# fire_warning_system.net
KiCad netlist of a schematic drawn in Altium Designer
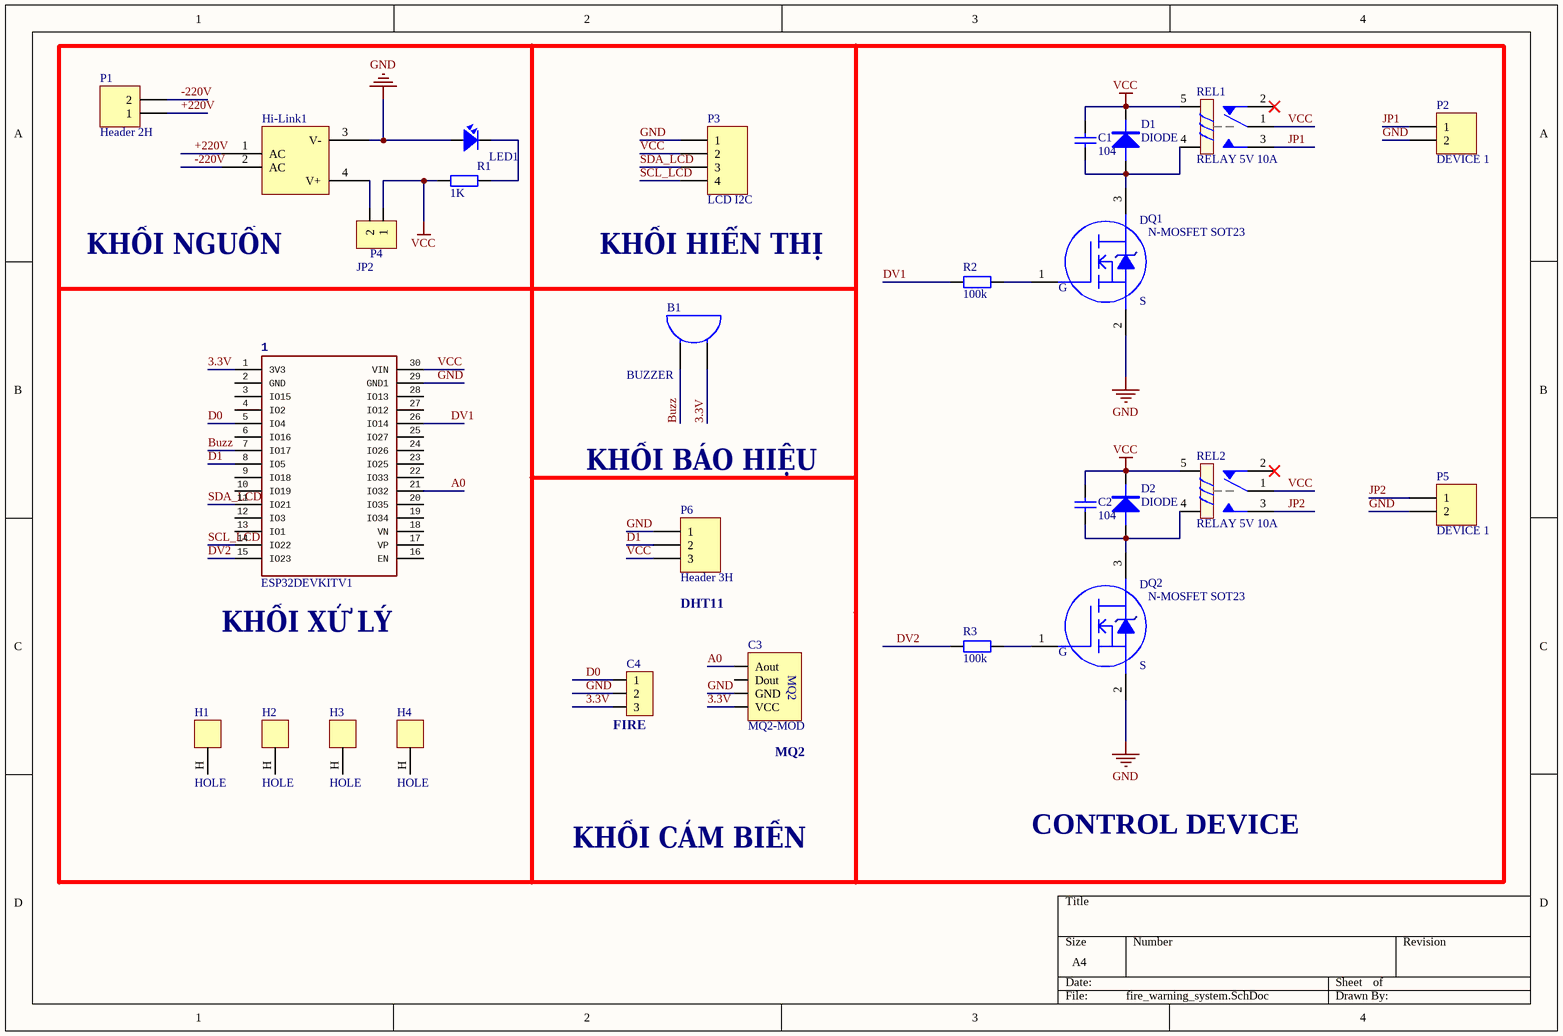
[diagram p0: fire_warning_system.SchDoc]

(export (version "E")
  (design (tool "Eeschema 10.0.6"))
  (components
    (comp (ref "1")
      (value "ESP32DEVKITV1")
      (footprint "ESP32-DEVKITV1")
      (libsource (lib "ESP32-DEVKITV1") (part "ESP32DEVKITV1"))
    )
    (comp (ref "B1")
      (value "BUZZER")
      (footprint "SPEAKER")
      (libsource (lib "ThinhNguyenLib") (part "BUZZER"))
    )
    (comp (ref "C1")
      (value "104")
      (footprint "0805 CAP")
      (fields (field (name "PUBLISHER") "Altium Limited"))
      (libsource (lib "THINHDUILIB") (part "CAP CERAMIC"))
    )
    (comp (ref "C2")
      (value "104")
      (footprint "0805 CAP")
      (fields (field (name "PUBLISHER") "Altium Limited"))
      (libsource (lib "THINHDUILIB") (part "CAP CERAMIC"))
    )
    (comp (ref "C3")
      (value "MQ2-MOD")
      (footprint "MQ2-MODULE")
      (fields
        (field (name "MANUFACTURER") "Würth Elektronik eiSos GmbH")
        (field (name "PARTNO") "613004143121")
        (field (name "CREATED BY") "Karrer Zheng")
      )
      (libsource (lib "LIBRARY") (part "MQ2-MOD"))
    )
    (comp (ref "C4")
      (value "Hồng ngoại")
      (footprint "JP3-C1T")
      (description "Header IDC, 3 x 1 Pin Vertical 2.54mm Pitch (Non-Boxed, Male)")
      (fields
        (field (name "MANUFACTURER") "Würth Elektronik eiSos GmbH")
        (field (name "PARTNO") "613002143121")
        (field (name "CREATED BY") "Karrer Zheng")
      )
      (libsource (lib "LIBRARY") (part "Header3"))
    )
    (comp (ref "D1") (value "DIODE") (footprint "DIODE SMA") (libsource (lib "THINHDUILIB") (part "DIODE")))
    (comp (ref "D2") (value "DIODE") (footprint "DIODE SMA") (libsource (lib "THINHDUILIB") (part "DIODE")))
    (comp (ref "H1") (value "HOLE") (footprint "HOLE") (libsource (lib "ThinhNguyenLib") (part "HOLE")))
    (comp (ref "H2") (value "HOLE") (footprint "HOLE") (libsource (lib "ThinhNguyenLib") (part "HOLE")))
    (comp (ref "H3") (value "HOLE") (footprint "HOLE") (libsource (lib "ThinhNguyenLib") (part "HOLE")))
    (comp (ref "H4") (value "HOLE") (footprint "HOLE") (libsource (lib "ThinhNguyenLib") (part "HOLE")))
    (comp (ref "Hi-Link1")
      (value "Component_1")
      (footprint "5/12V-3W")
      (libsource (lib "HI-LINK") (part "Component_1"))
    )
    (comp (ref "LED1")
      (value "LED")
      (footprint "LED SMD 0805")
      (description "LED Single colour Green and Red")
      (libsource (lib "LIBRARY") (part "LED"))
    )
    (comp (ref "P1")
      (value "Header 2H")
      (footprint "CON 2KF 5.08MM")
      (fields (field (name "PUBLISHER") "Altium Limited"))
      (libsource (lib "ThinhNguyenLib") (part "Header 2H"))
    )
    (comp (ref "P2")
      (value "DEVICE 1")
      (footprint "CON 2KF 5.08MM")
      (fields (field (name "PUBLISHER") "Altium Limited"))
      (libsource (lib "THINHDUILIB") (part "Header 2H"))
    )
    (comp (ref "P3")
      (value "LCD I2C")
      (footprint "HDR1X4")
      (fields (field (name "PUBLISHER") "Altium Limited"))
      (libsource (lib "ThinhNguyenLib") (part "Header 4H"))
    )
    (comp (ref "P4")
      (value "JP2")
      (footprint "JUMPER PITCH 2 PIN")
      (description "WR-PHD 2.54 mm Angled Socket Header")
      (fields
        (field (name "MANUFACTURER") "Würth Elektronik eiSos GmbH")
        (field (name "PARTNO") "613002143121")
        (field (name "CREATED BY") "Karrer Zheng")
      )
      (libsource (lib "LIBRARY") (part "JP2"))
    )
    (comp (ref "P5")
      (value "DEVICE 1")
      (footprint "CON 2KF 5.08MM")
      (fields (field (name "PUBLISHER") "Altium Limited"))
      (libsource (lib "THINHDUILIB") (part "Header 2H"))
    )
    (comp (ref "P6")
      (value "Header 3H")
      (footprint "HDR1X3")
      (fields (field (name "PUBLISHER") "Altium Limited"))
      (libsource (lib "ThinhNguyenLib") (part "Header 3H"))
    )
    (comp (ref "Q1")
      (value "N-MOSFET SOT23")
      (footprint "TO-92 - 2N7000")
      (libsource (lib "ThinhNguyenLib") (part "N-MOSFET SOT23"))
    )
    (comp (ref "Q2")
      (value "N-MOSFET SOT23")
      (footprint "TO-92 - 2N7000")
      (libsource (lib "ThinhNguyenLib") (part "N-MOSFET SOT23"))
    )
    (comp (ref "R1")
      (value "1K")
      (footprint "0805 RESISTOR")
      (libsource (lib "ThinhNguyenLib") (part "RESISTOR"))
    )
    (comp (ref "R2")
      (value "100k")
      (footprint "0805 RESISTOR")
      (libsource (lib "THINHDUILIB") (part "RESISTOR"))
    )
    (comp (ref "R3")
      (value "100k")
      (footprint "0805 RESISTOR")
      (libsource (lib "THINHDUILIB") (part "RESISTOR"))
    )
    (comp (ref "REL1")
      (value "RELAY 5V 10A")
      (footprint "RELAY 5V-10A")
      (libsource (lib "ThinhNguyenLib") (part "RELAY 5V 10A"))
    )
    (comp (ref "REL2")
      (value "RELAY 5V 10A")
      (footprint "RELAY 5V-10A")
      (libsource (lib "ThinhNguyenLib") (part "RELAY 5V 10A"))
    )
  )
  (nets
    (net (code "1") (name "/+220V") (class "Default")
      (node (ref "Hi-Link1") (pin "1") (pinfunction "AC_1") (pintype "passive"))
      (node (ref "P1") (pin "1") (pinfunction "1_1") (pintype "passive"))
    )
    (net (code "2") (name "/-220V") (class "Default")
      (node (ref "Hi-Link1") (pin "2") (pinfunction "AC_2") (pintype "passive"))
      (node (ref "P1") (pin "2") (pinfunction "2_2") (pintype "passive"))
    )
    (net (code "3") (name "/3.3V") (class "Default")
      (node (ref "1") (pin "1") (pinfunction "3V3_1") (pintype "passive"))
      (node (ref "B1") (pin "2") (pinfunction "B_2") (pintype "passive"))
      (node (ref "C3") (pin "4") (pinfunction "VCC_4") (pintype "passive"))
      (node (ref "C4") (pin "3") (pinfunction "3_3") (pintype "passive"))
    )
    (net (code "4") (name "/A0") (class "Default")
      (node (ref "1") (pin "21") (pinfunction "IO32_21") (pintype "passive"))
      (node (ref "C3") (pin "1") (pinfunction "Aout_1") (pintype "passive"))
    )
    (net (code "5") (name "/Buzz") (class "Default")
      (node (ref "1") (pin "7") (pinfunction "IO17_7") (pintype "passive"))
      (node (ref "B1") (pin "1") (pinfunction "A_1") (pintype "passive"))
    )
    (net (code "6") (name "/D0") (class "Default")
      (node (ref "1") (pin "5") (pinfunction "IO4_5") (pintype "passive"))
      (node (ref "C4") (pin "1") (pinfunction "1_1") (pintype "passive"))
    )
    (net (code "7") (name "/D1") (class "Default")
      (node (ref "1") (pin "8") (pinfunction "IO5_8") (pintype "passive"))
      (node (ref "P6") (pin "2") (pinfunction "2_2") (pintype "passive"))
    )
    (net (code "8") (name "/DV1") (class "Default")
      (node (ref "1") (pin "26") (pinfunction "IO14_26") (pintype "passive"))
      (node (ref "R2") (pin "2") (pinfunction "2_2") (pintype "passive"))
    )
    (net (code "9") (name "/DV2") (class "Default")
      (node (ref "1") (pin "15") (pinfunction "IO23_15") (pintype "passive"))
      (node (ref "R3") (pin "2") (pinfunction "2_2") (pintype "passive"))
    )
    (net (code "10") (name "/JP1") (class "Default")
      (node (ref "P2") (pin "1") (pinfunction "1_1") (pintype "passive"))
      (node (ref "REL1") (pin "3") (pinfunction "3_3") (pintype "passive"))
    )
    (net (code "11") (name "/JP2") (class "Default")
      (node (ref "P5") (pin "1") (pinfunction "1_1") (pintype "passive"))
      (node (ref "REL2") (pin "3") (pinfunction "3_3") (pintype "passive"))
    )
    (net (code "12") (name "/SCL_LCD") (class "Default")
      (node (ref "1") (pin "14") (pinfunction "IO22_14") (pintype "passive"))
      (node (ref "P3") (pin "4") (pinfunction "4_4") (pintype "passive"))
    )
    (net (code "13") (name "/SDA_LCD") (class "Default")
      (node (ref "1") (pin "11") (pinfunction "IO21_11") (pintype "passive"))
      (node (ref "P3") (pin "3") (pinfunction "3_3") (pintype "passive"))
    )
    (net (code "14") (name "GND") (class "Default")
      (node (ref "1") (pin "29") (pinfunction "GND1_29") (pintype "passive"))
      (node (ref "C3") (pin "3") (pinfunction "GND_3") (pintype "passive"))
      (node (ref "C4") (pin "2") (pinfunction "2_2") (pintype "passive"))
      (node (ref "Hi-Link1") (pin "3") (pinfunction "V-_3") (pintype "passive"))
      (node (ref "LED1") (pin "1") (pinfunction "1_1") (pintype "passive"))
      (node (ref "P2") (pin "2") (pinfunction "2_2") (pintype "passive"))
      (node (ref "P3") (pin "1") (pinfunction "1_1") (pintype "passive"))
      (node (ref "P5") (pin "2") (pinfunction "2_2") (pintype "passive"))
      (node (ref "P6") (pin "1") (pinfunction "1_1") (pintype "passive"))
      (node (ref "Q1") (pin "2") (pinfunction "S_2") (pintype "passive"))
      (node (ref "Q2") (pin "2") (pinfunction "S_2") (pintype "passive"))
    )
    (net (code "15") (name "Net-(Hi-Link1-V+)") (class "Default")
      (node (ref "Hi-Link1") (pin "4") (pinfunction "V+_4") (pintype "passive"))
      (node (ref "P4") (pin "2") (pinfunction "2_2") (pintype "passive"))
    )
    (net (code "16") (name "Net-(LED1-Pad2)") (class "Default")
      (node (ref "LED1") (pin "2") (pinfunction "2_2") (pintype "passive"))
      (node (ref "R1") (pin "2") (pinfunction "2_2") (pintype "passive"))
    )
    (net (code "17") (name "Net-(Q1-D)") (class "Default")
      (node (ref "C1") (pin "2") (pinfunction "2_2") (pintype "passive"))
      (node (ref "D1") (pin "1") (pinfunction "1_1") (pintype "passive"))
      (node (ref "Q1") (pin "3") (pinfunction "D_3") (pintype "passive"))
      (node (ref "REL1") (pin "4") (pinfunction "4_4") (pintype "passive"))
    )
    (net (code "18") (name "Net-(Q1-G)") (class "Default")
      (node (ref "Q1") (pin "1") (pinfunction "G_1") (pintype "passive"))
      (node (ref "R2") (pin "1") (pinfunction "1_1") (pintype "passive"))
    )
    (net (code "19") (name "Net-(Q2-D)") (class "Default")
      (node (ref "C2") (pin "2") (pinfunction "2_2") (pintype "passive"))
      (node (ref "D2") (pin "1") (pinfunction "1_1") (pintype "passive"))
      (node (ref "Q2") (pin "3") (pinfunction "D_3") (pintype "passive"))
      (node (ref "REL2") (pin "4") (pinfunction "4_4") (pintype "passive"))
    )
    (net (code "20") (name "Net-(Q2-G)") (class "Default")
      (node (ref "Q2") (pin "1") (pinfunction "G_1") (pintype "passive"))
      (node (ref "R3") (pin "1") (pinfunction "1_1") (pintype "passive"))
    )
    (net (code "21") (name "VCC") (class "Default")
      (node (ref "1") (pin "30") (pinfunction "VIN_30") (pintype "passive"))
      (node (ref "C1") (pin "1") (pinfunction "1_1") (pintype "passive"))
      (node (ref "C2") (pin "1") (pinfunction "1_1") (pintype "passive"))
      (node (ref "D1") (pin "2") (pinfunction "2_2") (pintype "passive"))
      (node (ref "D2") (pin "2") (pinfunction "2_2") (pintype "passive"))
      (node (ref "P3") (pin "2") (pinfunction "2_2") (pintype "passive"))
      (node (ref "P4") (pin "1") (pinfunction "1_1") (pintype "passive"))
      (node (ref "P6") (pin "3") (pinfunction "3_3") (pintype "passive"))
      (node (ref "R1") (pin "1") (pinfunction "1_1") (pintype "passive"))
      (node (ref "REL1") (pin "1") (pinfunction "1_1") (pintype "passive"))
      (node (ref "REL1") (pin "5") (pinfunction "5_5") (pintype "passive"))
      (node (ref "REL2") (pin "1") (pinfunction "1_1") (pintype "passive"))
      (node (ref "REL2") (pin "5") (pinfunction "5_5") (pintype "passive"))
    )
    (net (code "22") (name "unconnected-(1-EN-Pad16)") (class "Default")
      (node (ref "1") (pin "16") (pinfunction "EN_16") (pintype "passive"))
    )
    (net (code "23") (name "unconnected-(1-GND-Pad2)") (class "Default")
      (node (ref "1") (pin "2") (pinfunction "GND_2") (pintype "passive"))
    )
    (net (code "24") (name "unconnected-(1-IO1-Pad13)") (class "Default")
      (node (ref "1") (pin "13") (pinfunction "IO1_13") (pintype "passive"))
    )
    (net (code "25") (name "unconnected-(1-IO2-Pad4)") (class "Default")
      (node (ref "1") (pin "4") (pinfunction "IO2_4") (pintype "passive"))
    )
    (net (code "26") (name "unconnected-(1-IO3-Pad12)") (class "Default")
      (node (ref "1") (pin "12") (pinfunction "IO3_12") (pintype "passive"))
    )
    (net (code "27") (name "unconnected-(1-IO12-Pad27)") (class "Default")
      (node (ref "1") (pin "27") (pinfunction "IO12_27") (pintype "passive"))
    )
    (net (code "28") (name "unconnected-(1-IO13-Pad28)") (class "Default")
      (node (ref "1") (pin "28") (pinfunction "IO13_28") (pintype "passive"))
    )
    (net (code "29") (name "unconnected-(1-IO15-Pad3)") (class "Default")
      (node (ref "1") (pin "3") (pinfunction "IO15_3") (pintype "passive"))
    )
    (net (code "30") (name "unconnected-(1-IO16-Pad6)") (class "Default")
      (node (ref "1") (pin "6") (pinfunction "IO16_6") (pintype "passive"))
    )
    (net (code "31") (name "unconnected-(1-IO18-Pad9)") (class "Default")
      (node (ref "1") (pin "9") (pinfunction "IO18_9") (pintype "passive"))
    )
    (net (code "32") (name "unconnected-(1-IO19-Pad10)") (class "Default")
      (node (ref "1") (pin "10") (pinfunction "IO19_10") (pintype "passive"))
    )
    (net (code "33") (name "unconnected-(1-IO25-Pad23)") (class "Default")
      (node (ref "1") (pin "23") (pinfunction "IO25_23") (pintype "passive"))
    )
    (net (code "34") (name "unconnected-(1-IO26-Pad24)") (class "Default")
      (node (ref "1") (pin "24") (pinfunction "IO26_24") (pintype "passive"))
    )
    (net (code "35") (name "unconnected-(1-IO27-Pad25)") (class "Default")
      (node (ref "1") (pin "25") (pinfunction "IO27_25") (pintype "passive"))
    )
    (net (code "36") (name "unconnected-(1-IO33-Pad22)") (class "Default")
      (node (ref "1") (pin "22") (pinfunction "IO33_22") (pintype "passive"))
    )
    (net (code "37") (name "unconnected-(1-IO34-Pad19)") (class "Default")
      (node (ref "1") (pin "19") (pinfunction "IO34_19") (pintype "passive"))
    )
    (net (code "38") (name "unconnected-(1-IO35-Pad20)") (class "Default")
      (node (ref "1") (pin "20") (pinfunction "IO35_20") (pintype "passive"))
    )
    (net (code "39") (name "unconnected-(1-VN-Pad18)") (class "Default")
      (node (ref "1") (pin "18") (pinfunction "VN_18") (pintype "passive"))
    )
    (net (code "40") (name "unconnected-(1-VP-Pad17)") (class "Default")
      (node (ref "1") (pin "17") (pinfunction "VP_17") (pintype "passive"))
    )
    (net (code "41") (name "unconnected-(C3-Dout-Pad2)") (class "Default")
      (node (ref "C3") (pin "2") (pinfunction "Dout_2") (pintype "passive"))
    )
    (net (code "42") (name "unconnected-(H1-HOLE-PadH)") (class "Default")
      (node (ref "H1") (pin "H") (pinfunction "HOLE_H") (pintype "passive"))
    )
    (net (code "43") (name "unconnected-(H2-HOLE-PadH)") (class "Default")
      (node (ref "H2") (pin "H") (pinfunction "HOLE_H") (pintype "passive"))
    )
    (net (code "44") (name "unconnected-(H3-HOLE-PadH)") (class "Default")
      (node (ref "H3") (pin "H") (pinfunction "HOLE_H") (pintype "passive"))
    )
    (net (code "45") (name "unconnected-(H4-HOLE-PadH)") (class "Default")
      (node (ref "H4") (pin "H") (pinfunction "HOLE_H") (pintype "passive"))
    )
    (net (code "46") (name "unconnected-(REL1-Pad2)") (class "Default")
      (node (ref "REL1") (pin "2") (pinfunction "2_2") (pintype "passive+no_connect"))
    )
    (net (code "47") (name "unconnected-(REL2-Pad2)") (class "Default")
      (node (ref "REL2") (pin "2") (pinfunction "2_2") (pintype "passive+no_connect"))
    )
  )
)
